# USB_SPI_Flash.net
KiCad netlist of a schematic drawn in Altium Designer
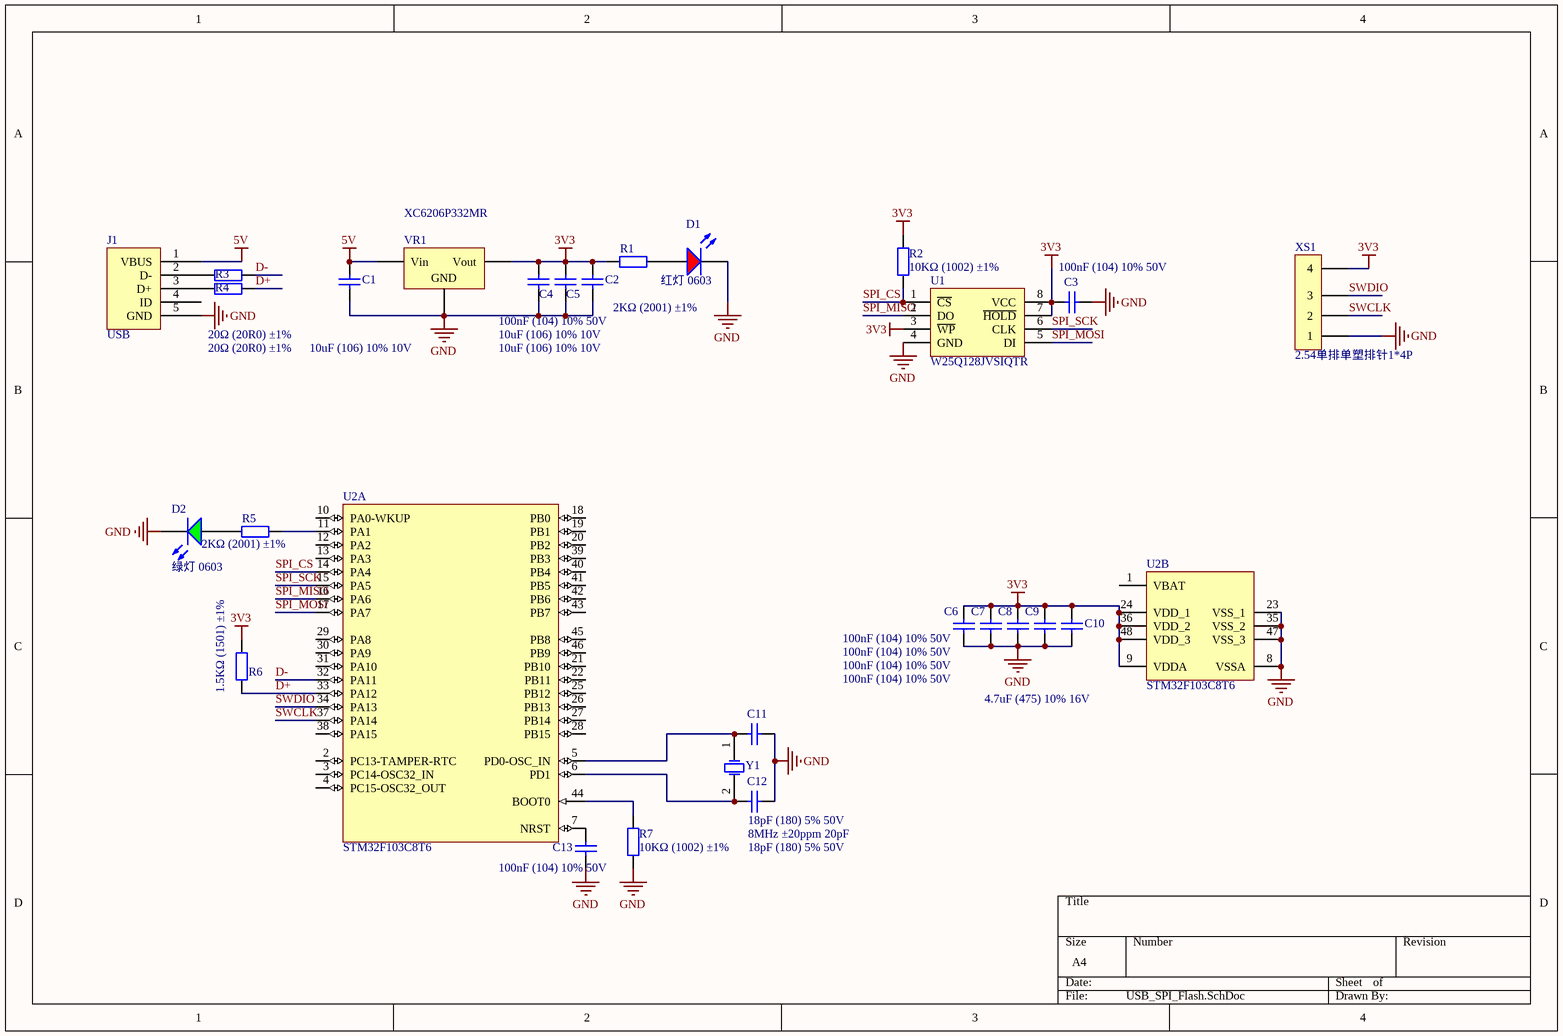
[diagram p0: USB_SPI_Flash.SchDoc]

(export (version "E")
  (design (tool "Eeschema 10.0.6"))
  (components
    (comp (ref "C1")
      (value "10uF (106) 10% 10V")
      (footprint "0603_C")
      (description "贴片电容")
      (libsource (lib "Cap") (part "0603 10uF (106) 10% 10V"))
    )
    (comp (ref "C2")
      (value "100nF (104) 10% 50V")
      (footprint "0603_C")
      (description "贴片电容")
      (libsource (lib "Cap") (part "0603 100nF (104) 10% 50V"))
    )
    (comp (ref "C3")
      (value "100nF (104) 10% 50V")
      (footprint "0603_C")
      (description "贴片电容")
      (libsource (lib "Cap") (part "0603 100nF (104) 10% 50V"))
    )
    (comp (ref "C4")
      (value "10uF (106) 10% 10V")
      (footprint "0603_C")
      (description "贴片电容")
      (libsource (lib "Cap") (part "0603 10uF (106) 10% 10V"))
    )
    (comp (ref "C5")
      (value "10uF (106) 10% 10V")
      (footprint "0603_C")
      (description "贴片电容")
      (libsource (lib "Cap") (part "0603 10uF (106) 10% 10V"))
    )
    (comp (ref "C6")
      (value "100nF (104) 10% 50V")
      (footprint "0603_C")
      (description "贴片电容")
      (libsource (lib "Cap") (part "0603 100nF (104) 10% 50V"))
    )
    (comp (ref "C7")
      (value "100nF (104) 10% 50V")
      (footprint "0603_C")
      (description "贴片电容")
      (libsource (lib "Cap") (part "0603 100nF (104) 10% 50V"))
    )
    (comp (ref "C8")
      (value "100nF (104) 10% 50V")
      (footprint "0603_C")
      (description "贴片电容")
      (libsource (lib "Cap") (part "0603 100nF (104) 10% 50V"))
    )
    (comp (ref "C9")
      (value "100nF (104) 10% 50V")
      (footprint "0603_C")
      (description "贴片电容")
      (libsource (lib "Cap") (part "0603 100nF (104) 10% 50V"))
    )
    (comp (ref "C10")
      (value "4.7uF (475) 10% 16V")
      (footprint "0603_C")
      (description "贴片电容")
      (libsource (lib "Cap") (part "0603 4.7uF (475) 10% 16V"))
    )
    (comp (ref "C11")
      (value "18pF (180) 5% 50V")
      (footprint "0603_C")
      (description "贴片电容")
      (libsource (lib "Cap") (part "0603 18pF (180) 5% 50V"))
    )
    (comp (ref "C12")
      (value "18pF (180) 5% 50V")
      (footprint "0603_C")
      (description "贴片电容")
      (libsource (lib "Cap") (part "0603 18pF (180) 5% 50V"))
    )
    (comp (ref "C13")
      (value "100nF (104) 10% 50V")
      (footprint "0603_C")
      (description "贴片电容")
      (libsource (lib "Cap") (part "0603 100nF (104) 10% 50V"))
    )
    (comp (ref "D1")
      (value "红灯 0603")
      (footprint "0603_LED_S1")
      (description "发光二极管")
      (libsource (lib "LED") (part "0603 红灯"))
    )
    (comp (ref "D2")
      (value "绿灯 0603")
      (footprint "0603_LED_S1")
      (description "发光二极管")
      (libsource (lib "LED") (part "0603 绿灯"))
    )
    (comp (ref "J1")
      (value "USB")
      (footprint "GOLDFIGER_FPC_8")
      (libsource (lib "USB_SPI_Flash") (part "USB"))
    )
    (comp (ref "R1")
      (value "2KΩ (2001) ±1%")
      (footprint "0603_R")
      (description "贴片电阻")
      (libsource (lib "RES") (part "0603 2KΩ (2001) 1%"))
    )
    (comp (ref "R2")
      (value "10KΩ (1002) ±1%")
      (footprint "0603_R")
      (description "贴片电阻")
      (libsource (lib "RES") (part "0603 10KΩ (1002) 1%"))
    )
    (comp (ref "R3")
      (value "20Ω (20R0) ±1%")
      (footprint "0603_R")
      (description "贴片电阻")
      (libsource (lib "RES") (part "0603 20Ω (20R0) 1%"))
    )
    (comp (ref "R4")
      (value "20Ω (20R0) ±1%")
      (footprint "0603_R")
      (description "贴片电阻")
      (libsource (lib "RES") (part "0603 20Ω (20R0) 1%"))
    )
    (comp (ref "R5")
      (value "2KΩ (2001) ±1%")
      (footprint "0603_R")
      (description "贴片电阻")
      (libsource (lib "RES") (part "0603 2KΩ (2001) 1%"))
    )
    (comp (ref "R6")
      (value "1.5KΩ (1501) ±1%")
      (footprint "0603_R")
      (description "贴片电阻")
      (libsource (lib "RES") (part "0603 1.5KΩ (1501) 1%"))
    )
    (comp (ref "R7")
      (value "10KΩ (1002) ±1%")
      (footprint "0603_R")
      (description "贴片电阻")
      (libsource (lib "RES") (part "0603 10KΩ (1002) 1%"))
    )
    (comp (ref "U1")
      (value "W25Q128JVSIQTR")
      (footprint "SOIC-8_208mil")
      (description "Flash ROM")
      (libsource (lib "IC") (part "W25Q128JVSIQTR_[C97521]"))
    )
    (comp (ref "U2")
      (value "STM32F103C8T6")
      (footprint "LQFP-48_7x7x05P")
      (description "ARM")
      (libsource (lib "MCU") (part "STM32F103C8T6"))
    )
    (comp (ref "VR1")
      (value "XC6206P332MR")
      (footprint "SOT-23-3L")
      (description "低压差线性稳压(LDO)")
      (libsource (lib "LDO") (part "SOT-23 XC6206P332MR"))
    )
    (comp (ref "XS1")
      (value "2.54单排单塑排针1*4P")
      (footprint "PIN4")
      (libsource (lib "Sdkd_schlib") (part "2.54单排单塑排针1*4P"))
    )
    (comp (ref "Y1")
      (value "8MHz ±20ppm 20pF")
      (footprint "SMD-5032_2P")
      (description "贴片晶振")
      (libsource (lib "CrystalOscillator") (part "SMD-5032_2P 8MHz 20ppm 20pF"))
    )
  )
  (nets
    (net (code "1") (name "/D+") (class "Default")
      (node (ref "R4") (pin "2") (pinfunction "2_2") (pintype "passive"))
      (node (ref "R6") (pin "1") (pinfunction "1_1") (pintype "passive"))
      (node (ref "U2") (pin "33") (pinfunction "PA12_33") (pintype "bidirectional"))
    )
    (net (code "2") (name "/D-") (class "Default")
      (node (ref "R3") (pin "2") (pinfunction "2_2") (pintype "passive"))
      (node (ref "U2") (pin "32") (pinfunction "PA11_32") (pintype "bidirectional"))
    )
    (net (code "3") (name "/SPI_CS") (class "Default")
      (node (ref "R2") (pin "1") (pinfunction "1_1") (pintype "passive"))
      (node (ref "U1") (pin "1") (pinfunction "~{CS}_1") (pintype "passive"))
      (node (ref "U2") (pin "14") (pinfunction "PA4_14") (pintype "bidirectional"))
    )
    (net (code "4") (name "/SPI_MISO") (class "Default")
      (node (ref "U1") (pin "2") (pinfunction "DO_2") (pintype "passive"))
      (node (ref "U2") (pin "16") (pinfunction "PA6_16") (pintype "bidirectional"))
    )
    (net (code "5") (name "/SPI_MOSI") (class "Default")
      (node (ref "U1") (pin "5") (pinfunction "DI_5") (pintype "passive"))
      (node (ref "U2") (pin "17") (pinfunction "PA7_17") (pintype "bidirectional"))
    )
    (net (code "6") (name "/SPI_SCK") (class "Default")
      (node (ref "U1") (pin "6") (pinfunction "CLK_6") (pintype "passive"))
      (node (ref "U2") (pin "15") (pinfunction "PA5_15") (pintype "bidirectional"))
    )
    (net (code "7") (name "/SWCLK") (class "Default")
      (node (ref "U2") (pin "37") (pinfunction "PA14_37") (pintype "bidirectional"))
      (node (ref "XS1") (pin "2") (pinfunction "2_2") (pintype "passive"))
    )
    (net (code "8") (name "/SWDIO") (class "Default")
      (node (ref "U2") (pin "34") (pinfunction "PA13_34") (pintype "bidirectional"))
      (node (ref "XS1") (pin "3") (pinfunction "3_3") (pintype "passive"))
    )
    (net (code "9") (name "3V3") (class "Default")
      (node (ref "C10") (pin "2") (pinfunction "2_2") (pintype "passive"))
      (node (ref "C2") (pin "2") (pinfunction "2_2") (pintype "passive"))
      (node (ref "C3") (pin "2") (pinfunction "2_2") (pintype "passive"))
      (node (ref "C4") (pin "2") (pinfunction "2_2") (pintype "passive"))
      (node (ref "C5") (pin "2") (pinfunction "2_2") (pintype "passive"))
      (node (ref "C6") (pin "2") (pinfunction "2_2") (pintype "passive"))
      (node (ref "C7") (pin "2") (pinfunction "2_2") (pintype "passive"))
      (node (ref "C8") (pin "2") (pinfunction "2_2") (pintype "passive"))
      (node (ref "C9") (pin "2") (pinfunction "2_2") (pintype "passive"))
      (node (ref "R1") (pin "2") (pinfunction "2_2") (pintype "passive"))
      (node (ref "R2") (pin "2") (pinfunction "2_2") (pintype "passive"))
      (node (ref "R6") (pin "2") (pinfunction "2_2") (pintype "passive"))
      (node (ref "U1") (pin "3") (pinfunction "~{WP}_3") (pintype "passive"))
      (node (ref "U1") (pin "7") (pinfunction "~{HOLD}_7") (pintype "passive"))
      (node (ref "U1") (pin "8") (pinfunction "VCC_8") (pintype "passive"))
      (node (ref "U2") (pin "24") (pinfunction "VDD_1_24") (pintype "power_in"))
      (node (ref "U2") (pin "36") (pinfunction "VDD_2_36") (pintype "power_in"))
      (node (ref "U2") (pin "48") (pinfunction "VDD_3_48") (pintype "power_in"))
      (node (ref "U2") (pin "9") (pinfunction "VDDA_9") (pintype "power_in"))
      (node (ref "VR1") (pin "2") (pinfunction "Vout_2") (pintype "passive"))
      (node (ref "XS1") (pin "4") (pinfunction "4_4") (pintype "passive"))
    )
    (net (code "10") (name "5V") (class "Default")
      (node (ref "C1") (pin "2") (pinfunction "2_2") (pintype "passive"))
      (node (ref "J1") (pin "1") (pinfunction "VBUS_1") (pintype "passive"))
      (node (ref "VR1") (pin "3") (pinfunction "Vin_3") (pintype "passive"))
    )
    (net (code "11") (name "GND") (class "Default")
      (node (ref "C1") (pin "1") (pinfunction "1_1") (pintype "passive"))
      (node (ref "C10") (pin "1") (pinfunction "1_1") (pintype "passive"))
      (node (ref "C11") (pin "1") (pinfunction "1_1") (pintype "passive"))
      (node (ref "C12") (pin "1") (pinfunction "1_1") (pintype "passive"))
      (node (ref "C13") (pin "1") (pinfunction "1_1") (pintype "passive"))
      (node (ref "C2") (pin "1") (pinfunction "1_1") (pintype "passive"))
      (node (ref "C3") (pin "1") (pinfunction "1_1") (pintype "passive"))
      (node (ref "C4") (pin "1") (pinfunction "1_1") (pintype "passive"))
      (node (ref "C5") (pin "1") (pinfunction "1_1") (pintype "passive"))
      (node (ref "C6") (pin "1") (pinfunction "1_1") (pintype "passive"))
      (node (ref "C7") (pin "1") (pinfunction "1_1") (pintype "passive"))
      (node (ref "C8") (pin "1") (pinfunction "1_1") (pintype "passive"))
      (node (ref "C9") (pin "1") (pinfunction "1_1") (pintype "passive"))
      (node (ref "D1") (pin "K") (pinfunction "K_K") (pintype "passive"))
      (node (ref "D2") (pin "K") (pinfunction "K_K") (pintype "passive"))
      (node (ref "J1") (pin "5") (pinfunction "GND_5") (pintype "passive"))
      (node (ref "R7") (pin "1") (pinfunction "1_1") (pintype "passive"))
      (node (ref "U1") (pin "4") (pinfunction "GND_4") (pintype "passive"))
      (node (ref "U2") (pin "23") (pinfunction "VSS_1_23") (pintype "power_in"))
      (node (ref "U2") (pin "35") (pinfunction "VSS_2_35") (pintype "power_in"))
      (node (ref "U2") (pin "47") (pinfunction "VSS_3_47") (pintype "power_in"))
      (node (ref "U2") (pin "8") (pinfunction "VSSA_8") (pintype "power_in"))
      (node (ref "VR1") (pin "1") (pinfunction "GND_1") (pintype "passive"))
      (node (ref "XS1") (pin "1") (pinfunction "1_1") (pintype "passive"))
    )
    (net (code "12") (name "Net-(D1-PadA)") (class "Default")
      (node (ref "D1") (pin "A") (pinfunction "A_A") (pintype "passive"))
      (node (ref "R1") (pin "1") (pinfunction "1_1") (pintype "passive"))
    )
    (net (code "13") (name "Net-(D2-PadA)") (class "Default")
      (node (ref "D2") (pin "A") (pinfunction "A_A") (pintype "passive"))
      (node (ref "R5") (pin "2") (pinfunction "2_2") (pintype "passive"))
    )
    (net (code "14") (name "Net-(J1-D+)") (class "Default")
      (node (ref "J1") (pin "3") (pinfunction "D+_3") (pintype "passive"))
      (node (ref "R4") (pin "1") (pinfunction "1_1") (pintype "passive"))
    )
    (net (code "15") (name "Net-(J1-D-)") (class "Default")
      (node (ref "J1") (pin "2") (pinfunction "D-_2") (pintype "passive"))
      (node (ref "R3") (pin "1") (pinfunction "1_1") (pintype "passive"))
    )
    (net (code "16") (name "Net-(U2A-BOOT0)") (class "Default")
      (node (ref "R7") (pin "2") (pinfunction "2_2") (pintype "passive"))
      (node (ref "U2") (pin "44") (pinfunction "BOOT0_44") (pintype "input"))
    )
    (net (code "17") (name "Net-(U2A-NRST)") (class "Default")
      (node (ref "C13") (pin "2") (pinfunction "2_2") (pintype "passive"))
      (node (ref "U2") (pin "7") (pinfunction "NRST_7") (pintype "bidirectional"))
    )
    (net (code "18") (name "Net-(U2A-PA1)") (class "Default")
      (node (ref "R5") (pin "1") (pinfunction "1_1") (pintype "passive"))
      (node (ref "U2") (pin "11") (pinfunction "PA1_11") (pintype "bidirectional"))
    )
    (net (code "19") (name "Net-(U2A-PD0-OSC_IN)") (class "Default")
      (node (ref "C11") (pin "2") (pinfunction "2_2") (pintype "passive"))
      (node (ref "U2") (pin "5") (pinfunction "PD0-OSC_IN_5") (pintype "bidirectional"))
      (node (ref "Y1") (pin "1") (pinfunction "OSC1_1") (pintype "passive"))
    )
    (net (code "20") (name "Net-(U2A-PD1)") (class "Default")
      (node (ref "C12") (pin "2") (pinfunction "2_2") (pintype "passive"))
      (node (ref "U2") (pin "6") (pinfunction "PD1_6") (pintype "bidirectional"))
      (node (ref "Y1") (pin "2") (pinfunction "OSC2_2") (pintype "passive"))
    )
    (net (code "21") (name "unconnected-(J1-ID-Pad4)") (class "Default")
      (node (ref "J1") (pin "4") (pinfunction "ID_4") (pintype "passive"))
    )
    (net (code "22") (name "unconnected-(U2A-PA0-WKUP-Pad10)") (class "Default")
      (node (ref "U2") (pin "10") (pinfunction "PA0-WKUP_10") (pintype "bidirectional"))
    )
    (net (code "23") (name "unconnected-(U2A-PA2-Pad12)") (class "Default")
      (node (ref "U2") (pin "12") (pinfunction "PA2_12") (pintype "bidirectional"))
    )
    (net (code "24") (name "unconnected-(U2A-PA3-Pad13)") (class "Default")
      (node (ref "U2") (pin "13") (pinfunction "PA3_13") (pintype "bidirectional"))
    )
    (net (code "25") (name "unconnected-(U2A-PA8-Pad29)") (class "Default")
      (node (ref "U2") (pin "29") (pinfunction "PA8_29") (pintype "bidirectional"))
    )
    (net (code "26") (name "unconnected-(U2A-PA9-Pad30)") (class "Default")
      (node (ref "U2") (pin "30") (pinfunction "PA9_30") (pintype "bidirectional"))
    )
    (net (code "27") (name "unconnected-(U2A-PA10-Pad31)") (class "Default")
      (node (ref "U2") (pin "31") (pinfunction "PA10_31") (pintype "bidirectional"))
    )
    (net (code "28") (name "unconnected-(U2A-PA15-Pad38)") (class "Default")
      (node (ref "U2") (pin "38") (pinfunction "PA15_38") (pintype "bidirectional"))
    )
    (net (code "29") (name "unconnected-(U2A-PB0-Pad18)") (class "Default")
      (node (ref "U2") (pin "18") (pinfunction "PB0_18") (pintype "bidirectional"))
    )
    (net (code "30") (name "unconnected-(U2A-PB1-Pad19)") (class "Default")
      (node (ref "U2") (pin "19") (pinfunction "PB1_19") (pintype "bidirectional"))
    )
    (net (code "31") (name "unconnected-(U2A-PB2-Pad20)") (class "Default")
      (node (ref "U2") (pin "20") (pinfunction "PB2_20") (pintype "bidirectional"))
    )
    (net (code "32") (name "unconnected-(U2A-PB3-Pad39)") (class "Default")
      (node (ref "U2") (pin "39") (pinfunction "PB3_39") (pintype "bidirectional"))
    )
    (net (code "33") (name "unconnected-(U2A-PB4-Pad40)") (class "Default")
      (node (ref "U2") (pin "40") (pinfunction "PB4_40") (pintype "bidirectional"))
    )
    (net (code "34") (name "unconnected-(U2A-PB5-Pad41)") (class "Default")
      (node (ref "U2") (pin "41") (pinfunction "PB5_41") (pintype "bidirectional"))
    )
    (net (code "35") (name "unconnected-(U2A-PB6-Pad42)") (class "Default")
      (node (ref "U2") (pin "42") (pinfunction "PB6_42") (pintype "bidirectional"))
    )
    (net (code "36") (name "unconnected-(U2A-PB7-Pad43)") (class "Default")
      (node (ref "U2") (pin "43") (pinfunction "PB7_43") (pintype "bidirectional"))
    )
    (net (code "37") (name "unconnected-(U2A-PB8-Pad45)") (class "Default")
      (node (ref "U2") (pin "45") (pinfunction "PB8_45") (pintype "bidirectional"))
    )
    (net (code "38") (name "unconnected-(U2A-PB9-Pad46)") (class "Default")
      (node (ref "U2") (pin "46") (pinfunction "PB9_46") (pintype "bidirectional"))
    )
    (net (code "39") (name "unconnected-(U2A-PB10-Pad21)") (class "Default")
      (node (ref "U2") (pin "21") (pinfunction "PB10_21") (pintype "bidirectional"))
    )
    (net (code "40") (name "unconnected-(U2A-PB11-Pad22)") (class "Default")
      (node (ref "U2") (pin "22") (pinfunction "PB11_22") (pintype "bidirectional"))
    )
    (net (code "41") (name "unconnected-(U2A-PB12-Pad25)") (class "Default")
      (node (ref "U2") (pin "25") (pinfunction "PB12_25") (pintype "bidirectional"))
    )
    (net (code "42") (name "unconnected-(U2A-PB13-Pad26)") (class "Default")
      (node (ref "U2") (pin "26") (pinfunction "PB13_26") (pintype "bidirectional"))
    )
    (net (code "43") (name "unconnected-(U2A-PB14-Pad27)") (class "Default")
      (node (ref "U2") (pin "27") (pinfunction "PB14_27") (pintype "bidirectional"))
    )
    (net (code "44") (name "unconnected-(U2A-PB15-Pad28)") (class "Default")
      (node (ref "U2") (pin "28") (pinfunction "PB15_28") (pintype "bidirectional"))
    )
    (net (code "45") (name "unconnected-(U2A-PC13-TAMPER-RTC-Pad2)") (class "Default")
      (node (ref "U2") (pin "2") (pinfunction "PC13-TAMPER-RTC_2") (pintype "bidirectional"))
    )
    (net (code "46") (name "unconnected-(U2A-PC14-OSC32_IN-Pad3)") (class "Default")
      (node (ref "U2") (pin "3") (pinfunction "PC14-OSC32_IN_3") (pintype "bidirectional"))
    )
    (net (code "47") (name "unconnected-(U2A-PC15-OSC32_OUT-Pad4)") (class "Default")
      (node (ref "U2") (pin "4") (pinfunction "PC15-OSC32_OUT_4") (pintype "bidirectional"))
    )
    (net (code "48") (name "unconnected-(U2B-VBAT-Pad1)") (class "Default")
      (node (ref "U2") (pin "1") (pinfunction "VBAT_1") (pintype "power_in"))
    )
  )
)
